# INSGPS.net
KiCad netlist of a schematic drawn in Altium Designer
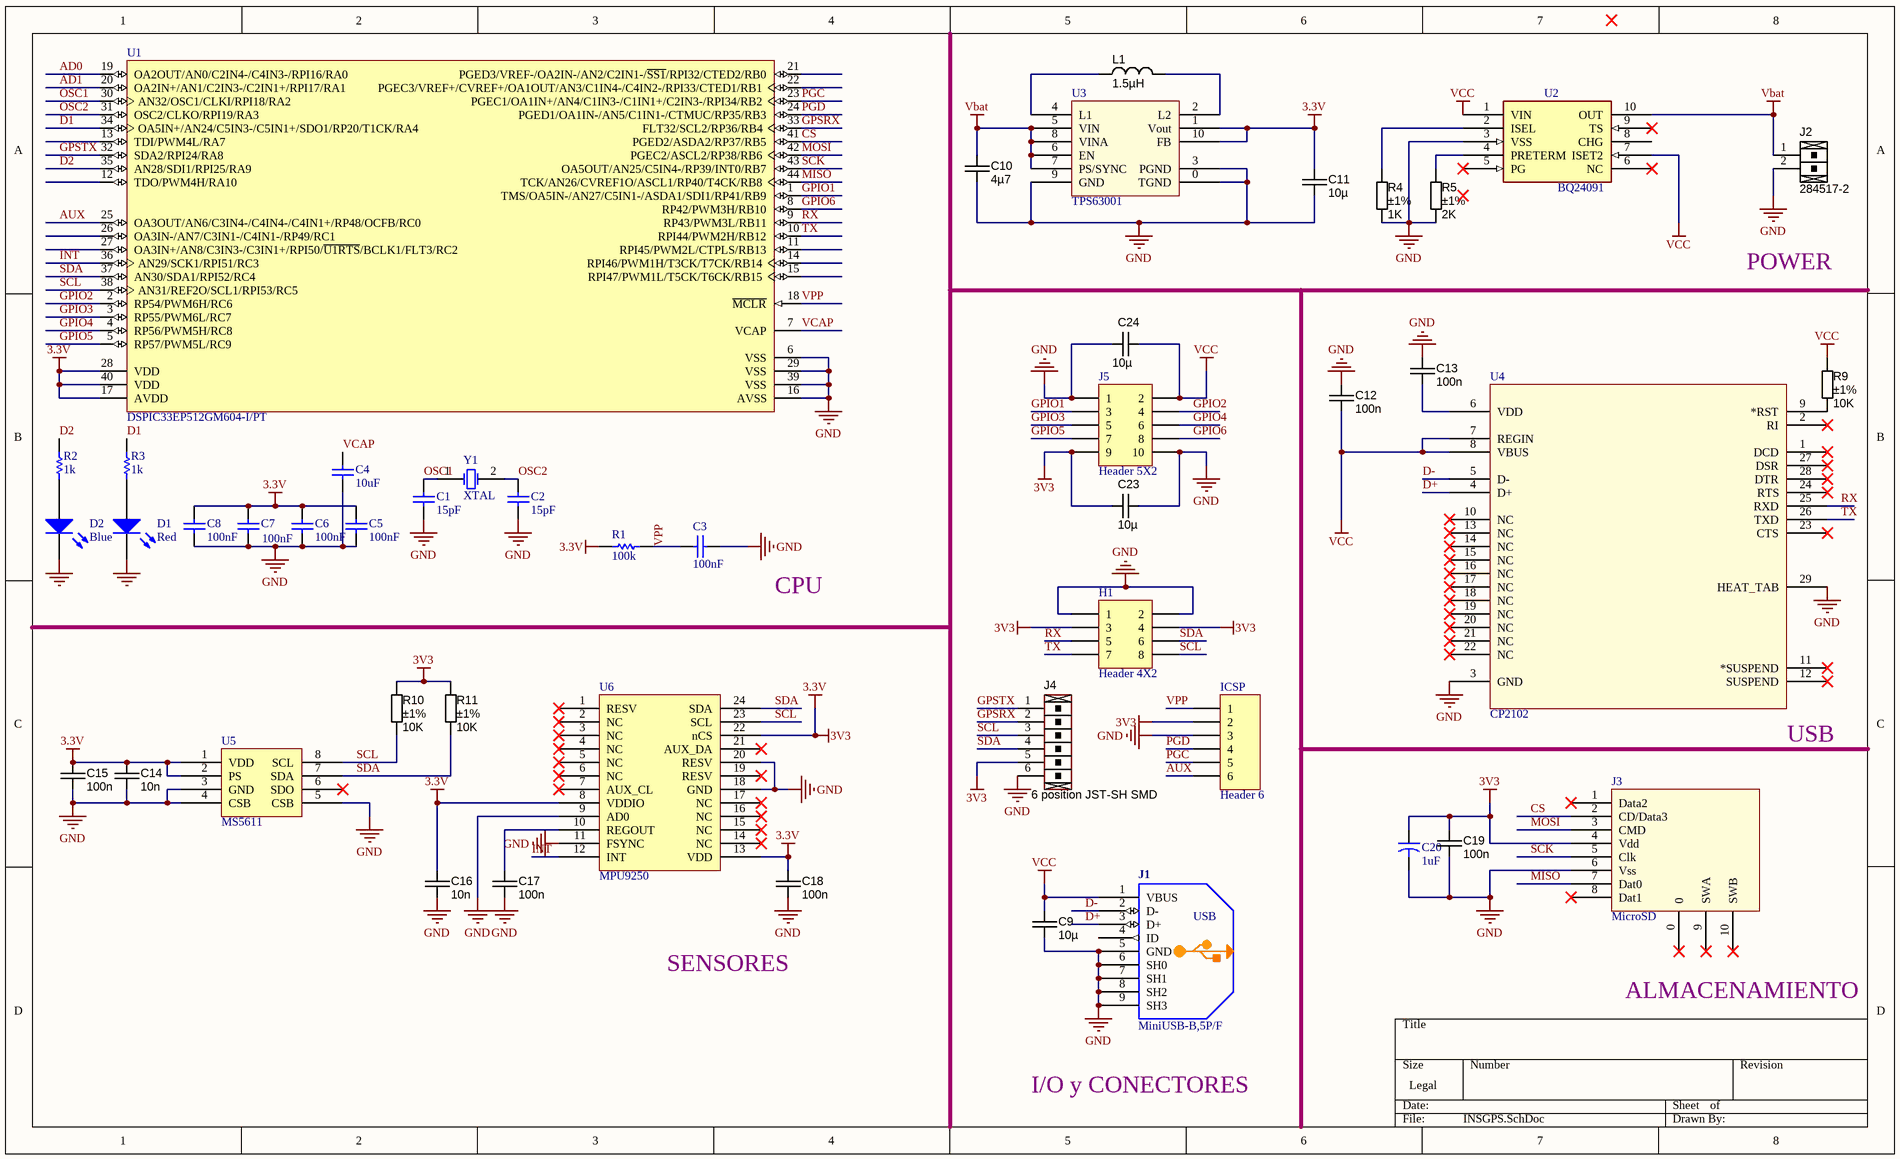
[diagram p0: INSGPS.SchDoc]

(export (version "E")
  (design (tool "Eeschema 10.0.6"))
  (components
    (comp (ref "C1")
      (value "15pF")
      (footprint "C0805")
      (description "Capacitor")
      (fields (field (name "PUBLISHER") "Altium Limited"))
      (libsource (lib "Miscellaneous Devices") (part "Cap"))
    )
    (comp (ref "C2")
      (value "15pF")
      (footprint "C0805")
      (description "Capacitor")
      (fields (field (name "PUBLISHER") "Altium Limited"))
      (libsource (lib "Miscellaneous Devices") (part "Cap"))
    )
    (comp (ref "C3")
      (value "100nF")
      (footprint "C0805")
      (description "Capacitor")
      (fields (field (name "PUBLISHER") "Altium Limited"))
      (libsource (lib "Miscellaneous Devices") (part "Cap"))
    )
    (comp (ref "C4")
      (value "10uF")
      (footprint "C0805")
      (description "Capacitor")
      (fields (field (name "PUBLISHER") "Altium Limited"))
      (libsource (lib "Miscellaneous Devices") (part "Cap"))
    )
    (comp (ref "C5")
      (value "100nF")
      (footprint "C0805")
      (description "Capacitor")
      (fields (field (name "PUBLISHER") "Altium Limited"))
      (libsource (lib "Miscellaneous Devices") (part "Cap"))
    )
    (comp (ref "C6")
      (value "100nF")
      (footprint "C0805")
      (description "Capacitor")
      (fields (field (name "PUBLISHER") "Altium Limited"))
      (libsource (lib "Miscellaneous Devices") (part "Cap"))
    )
    (comp (ref "C7")
      (value "100nF")
      (footprint "C0805")
      (description "Capacitor")
      (fields (field (name "PUBLISHER") "Altium Limited"))
      (libsource (lib "Miscellaneous Devices") (part "Cap"))
    )
    (comp (ref "C8")
      (value "100nF")
      (footprint "C0805")
      (description "Capacitor")
      (fields (field (name "PUBLISHER") "Altium Limited"))
      (libsource (lib "Miscellaneous Devices") (part "Cap"))
    )
    (comp (ref "C9")
      (value "10µ")
      (footprint "CAPC3216X180N")
      (description "Capacitor SMD Cer 10uF 10% 10V X5R 1206")
      (fields (field (name "TOLERANCE") "±10%"))
      (libsource (lib "PBL - Capacitors") (part "CAPC_10u_1206_10V"))
    )
    (comp (ref "C10")
      (value "4µ7")
      (footprint "CAPC2012X135N")
      (description "Capacitor SMD Cer 4.7uF 10% 16V X5R 0805")
      (fields (field (name "TOLERANCE") "±10%"))
      (libsource (lib "PBL - Capacitors") (part "CAPC_4u7_0805"))
    )
    (comp (ref "C11")
      (value "10µ")
      (footprint "CAPC3216X180N")
      (description "Capacitor SMD Cer 10uF 10% 10V X5R 1206")
      (fields (field (name "TOLERANCE") "±10%"))
      (libsource (lib "PBL - Capacitors") (part "CAPC_10u_1206_10V"))
    )
    (comp (ref "C12")
      (value "100n")
      (footprint "CAPC2012X135N")
      (description "Capacitor SMD Cer 100nF 10% 100V X7R 0805")
      (fields (field (name "TOLERANCE") "±10%"))
      (libsource (lib "PBL - Capacitors") (part "CAPC_100n_0805_X7R_100V_10%"))
    )
    (comp (ref "C13")
      (value "100n")
      (footprint "CAPC2012X135N")
      (description "Capacitor SMD Cer 100nF 10% 100V X7R 0805")
      (fields (field (name "TOLERANCE") "±10%"))
      (libsource (lib "PBL - Capacitors") (part "CAPC_100n_0805_X7R_100V_10%"))
    )
    (comp (ref "C14")
      (value "10n")
      (footprint "CAPC2012X135N")
      (description "Capacitor SMD Cer 100nF 10% 100V X7R 0805")
      (fields (field (name "TOLERANCE") "±10%"))
      (libsource (lib "PBL - Capacitors") (part "CAPC_100n_0805_X7R_100V_10%"))
    )
    (comp (ref "C15")
      (value "100n")
      (footprint "CAPC2012X135N")
      (description "Capacitor SMD Cer 100nF 10% 100V X7R 0805")
      (fields (field (name "TOLERANCE") "±10%"))
      (libsource (lib "PBL - Capacitors") (part "CAPC_100n_0805_X7R_100V_10%"))
    )
    (comp (ref "C16")
      (value "10n")
      (footprint "CAPC2012X135N")
      (description "Capacitor SMD Cer 100nF 10% 100V X7R 0805")
      (fields (field (name "TOLERANCE") "±10%"))
      (libsource (lib "PBL - Capacitors") (part "CAPC_100n_0805_X7R_100V_10%"))
    )
    (comp (ref "C17")
      (value "100n")
      (footprint "CAPC2012X135N")
      (description "Capacitor SMD Cer 100nF 10% 100V X7R 0805")
      (fields (field (name "TOLERANCE") "±10%"))
      (libsource (lib "PBL - Capacitors") (part "CAPC_100n_0805_X7R_100V_10%"))
    )
    (comp (ref "C18")
      (value "100n")
      (footprint "CAPC2012X135N")
      (description "Capacitor SMD Cer 100nF 10% 100V X7R 0805")
      (fields (field (name "TOLERANCE") "±10%"))
      (libsource (lib "PBL - Capacitors") (part "CAPC_100n_0805_X7R_100V_10%"))
    )
    (comp (ref "C19")
      (value "100n")
      (footprint "CAPC2012X135N")
      (description "Capacitor SMD Cer 100nF 10% 100V X7R 0805")
      (fields (field (name "TOLERANCE") "±10%"))
      (libsource (lib "PBL - Capacitors") (part "CAPC_100n_0805_X7R_100V_10%"))
    )
    (comp (ref "C20")
      (value "1uF")
      (footprint "CC3216-1206")
      (description "Capacitor Tantalium 1206")
      (fields (field (name "PUBLISHER") "Altium Limited"))
      (libsource (lib "Miscellaneous Devices") (part "Cap2"))
    )
    (comp (ref "C23")
      (value "10µ")
      (footprint "CAPC3216X180N")
      (description "Capacitor SMD Cer 10uF 10% 10V X5R 1206")
      (fields (field (name "TOLERANCE") "±10%"))
      (libsource (lib "PBL - Capacitors") (part "CAPC_10u_1206_10V"))
    )
    (comp (ref "C24")
      (value "10µ")
      (footprint "CAPC3216X180N")
      (description "Capacitor SMD Cer 10uF 10% 10V X5R 1206")
      (fields (field (name "TOLERANCE") "±10%"))
      (libsource (lib "PBL - Capacitors") (part "CAPC_10u_1206_10V"))
    )
    (comp (ref "D1")
      (value "Red")
      (footprint "0805 LED RED")
      (description "Typical BLUE SiC LED")
      (fields (field (name "PUBLISHER") "Altium Limited"))
      (libsource (lib "Miscellaneous Devices") (part "LED3"))
    )
    (comp (ref "D2")
      (value "Blue")
      (footprint "0805 LED RED")
      (description "Typical BLUE SiC LED")
      (fields (field (name "PUBLISHER") "Altium Limited"))
      (libsource (lib "Miscellaneous Devices") (part "LED3"))
    )
    (comp (ref "H1")
      (value "Header 4X2")
      (footprint "HDR2X4")
      (description "Header, 4-Pin, Dual row")
      (fields (field (name "PUBLISHER") "Altium Limited"))
      (libsource (lib "Miscellaneous Connectors") (part "Header 4X2"))
    )
    (comp (ref "ICSP")
      (value "Header 6")
      (footprint "HDR1X6")
      (description "Header, 6-Pin")
      (fields (field (name "PUBLISHER") "Altium Limited"))
      (libsource (lib "Miscellaneous Connectors") (part "Header 6"))
    )
    (comp (ref "J1")
      (value "MiniUSB-B,5P/F")
      (footprint "USB_MINIB_SMT")
      (description "MiniUSB-B,5P/F,7.6×9×4,SMD,RoHS")
      (fields (field (name "Comment") "USB_MINIB_SMT"))
      (libsource (lib "EasyARM-i.MX283-EV") (part "USB_MINIB_SMT"))
    )
    (comp (ref "J2")
      (value "ST 2 pins 1mm pitch")
      (footprint "S2B-PH-K-S")
      (description "Terminal Block THT 2-position header 3.81mm pitch")
      (fields (field (name "VOLTAGE") "300V") (field (name "MANUFACTURER PART NUMBER 1") "284517-2"))
      (libsource (lib "PBL - Connectors") (part "2P_TERM_BLOCK_HEADER"))
    )
    (comp (ref "J3") (value "MicroSD") (footprint "SD CARD") (libsource (lib "TexasLib") (part "MicroSD")))
    (comp (ref "J4")
      (value "6 position JST-SH SMD")
      (footprint "SM06B-SRSS-TB")
      (description "JST-SH, 6-Position connector, 1mm pitch")
      (fields (field (name "VOLTAGE") "300V"))
      (libsource (lib "PBL - Connectors") (part "6P_TERM BLOCK HEADER"))
    )
    (comp (ref "J5")
      (value "Header 5X2")
      (footprint "HDR2X5")
      (description "Header, 5-Pin, Dual row")
      (fields (field (name "PUBLISHER") "Altium Limited"))
      (libsource (lib "Miscellaneous Connectors") (part "Header 5X2"))
    )
    (comp (ref "L1")
      (value "1.5µH")
      (footprint "IND_COILCRAFT_LPS3015")
      (description "Inductor SMD Low DCR 10 µH 900mA 20% 1210")
      (fields (field (name "TOLERANCE") "±20%"))
      (libsource (lib "PBL - Inductors") (part "INDC_10u_LowRDC"))
    )
    (comp (ref "R1")
      (value "100k")
      (footprint "6-0805_M")
      (description "Chip Resistor 0805")
      (fields (field (name "PUBLISHER") "Altium Limited"))
      (libsource (lib "Miscellaneous Devices") (part "Res1"))
    )
    (comp (ref "R2")
      (value "1k")
      (footprint "6-0805_M")
      (description "Chip Resistor 0805")
      (fields (field (name "PUBLISHER") "Altium Limited"))
      (libsource (lib "Miscellaneous Devices") (part "Res1"))
    )
    (comp (ref "R3")
      (value "1k")
      (footprint "6-0805_M")
      (description "Chip Resistor 0805")
      (fields (field (name "PUBLISHER") "Altium Limited"))
      (libsource (lib "Miscellaneous Devices") (part "Res1"))
    )
    (comp (ref "R4")
      (value "1K")
      (footprint "RESC2012X70N")
      (description "Resistor SMD chip 1k Ohm 0.125W 1% 0805")
      (fields (field (name "TOLERANCE") "±1%"))
      (libsource (lib "PBL - Resistors") (part "RES_1K_0805_1%"))
    )
    (comp (ref "R5")
      (value "2K")
      (footprint "RESC2012X70N")
      (description "Resistor SMD chip 1k Ohm 0.125W 1% 0805")
      (fields (field (name "TOLERANCE") "±1%"))
      (libsource (lib "PBL - Resistors") (part "RES_1K_0805_1%"))
    )
    (comp (ref "R9")
      (value "10K")
      (footprint "RESC2012X70N")
      (description "Resistor SMD chip 1k Ohm 0.125W 1% 0805")
      (fields (field (name "TOLERANCE") "±1%"))
      (libsource (lib "PBL - Resistors") (part "RES_1K_0805_1%"))
    )
    (comp (ref "R10")
      (value "10K")
      (footprint "RESC2012X70N")
      (description "Resistor SMD chip 1k Ohm 0.125W 1% 0805")
      (fields (field (name "TOLERANCE") "±1%"))
      (libsource (lib "PBL - Resistors") (part "RES_1K_0805_1%"))
    )
    (comp (ref "R11")
      (value "10K")
      (footprint "RESC2012X70N")
      (description "Resistor SMD chip 1k Ohm 0.125W 1% 0805")
      (fields (field (name "TOLERANCE") "±1%"))
      (libsource (lib "PBL - Resistors") (part "RES_1K_0805_1%"))
    )
    (comp (ref "U1")
      (value "DSPIC33EP512GM604-I/PT")
      (footprint "TQFP-44")
      (fields (field (name "MANUFACTURER") "Microchip"))
      (libsource (lib "Microchip dsPIC33E") (part "DSPIC33EP512GM604-I/PT"))
    )
    (comp (ref "U2")
      (value "BQ24091")
      (footprint "10MSOP-PowerPAD")
      (libsource (lib "ESQUEMATICOS") (part "BQ2409X"))
    )
    (comp (ref "U3")
      (value "TPS63001")
      (footprint "TDFN-EP 10")
      (libsource (lib "ESQUEMATICOS") (part "TPS6303X"))
    )
    (comp (ref "U4")
      (value "CP2102")
      (footprint "QFN50P400X400X95-28N")
      (libsource (lib "ESQUEMATICOS") (part "CP2102"))
    )
    (comp (ref "U5")
      (value "MS5611")
      (footprint "MS5611")
      (description "Sensor digital de presion barometrica absoluta con interfaz I2C")
      (libsource (lib "ESQUEMATICOS") (part "MS5611"))
    )
    (comp (ref "U6")
      (value "MPU9250")
      (footprint "QFN50P400X400X95-24N")
      (libsource (lib "ESQUEMATICOS") (part "MPU9250"))
    )
    (comp (ref "Y1")
      (value "XTAL")
      (footprint "CRYSTAL_NX5032GA / NX5032GB")
      (description "Crystal Oscillator")
      (fields (field (name "PUBLISHER") "Altium Limited"))
      (libsource (lib "Miscellaneous Devices") (part "XTAL"))
    )
  )
  (nets
    (net (code "1") (name "/AD0") (class "Default")
      (node (ref "U1") (pin "19") (pinfunction "OA2OUT/AN0/C2IN4-/C4IN3-/RPI16/RA0_19") (pintype "bidirectional"))
    )
    (net (code "2") (name "/AD1") (class "Default")
      (node (ref "U1") (pin "20") (pinfunction "OA2IN+/AN1/C2IN3-/C2IN1+/RPI17/RA1_20") (pintype "bidirectional"))
    )
    (net (code "3") (name "/AUX") (class "Default")
      (node (ref "ICSP") (pin "6") (pinfunction "6_6") (pintype "passive"))
      (node (ref "U1") (pin "25") (pinfunction "OA3OUT/AN6/C3IN4-/C4IN4-/C4IN1+/RP48/OCFB/RC0_25") (pintype "bidirectional"))
    )
    (net (code "4") (name "/CS") (class "Default")
      (node (ref "J3") (pin "2") (pinfunction "CD/Data3_2") (pintype "passive"))
      (node (ref "U1") (pin "41") (pinfunction "PGED2/ASDA2/RP37/RB5_41") (pintype "bidirectional"))
    )
    (net (code "5") (name "/D+") (class "Default")
      (node (ref "J1") (pin "3") (pinfunction "D+_3") (pintype "bidirectional"))
      (node (ref "U4") (pin "4") (pinfunction "D+_4") (pintype "passive"))
    )
    (net (code "6") (name "/D-") (class "Default")
      (node (ref "J1") (pin "2") (pinfunction "D-_2") (pintype "bidirectional"))
      (node (ref "U4") (pin "5") (pinfunction "D-_5") (pintype "passive"))
    )
    (net (code "7") (name "/D1") (class "Default")
      (node (ref "R3") (pin "1") (pinfunction "1_1") (pintype "passive"))
      (node (ref "U1") (pin "34") (pinfunction "OA5IN+/AN24/C5IN3-/C5IN1+/SDO1/RP20/T1CK/RA4_34") (pintype "bidirectional"))
    )
    (net (code "8") (name "/D2") (class "Default")
      (node (ref "R2") (pin "1") (pinfunction "1_1") (pintype "passive"))
      (node (ref "U1") (pin "35") (pinfunction "AN28/SDI1/RPI25/RA9_35") (pintype "bidirectional"))
    )
    (net (code "9") (name "/GPIO1") (class "Default")
      (node (ref "J5") (pin "3") (pinfunction "3_3") (pintype "passive"))
      (node (ref "U1") (pin "1") (pinfunction "TMS/OA5IN-/AN27/C5IN1-/ASDA1/SDI1/RP41/RB9_1") (pintype "bidirectional"))
    )
    (net (code "10") (name "/GPIO2") (class "Default")
      (node (ref "J5") (pin "4") (pinfunction "4_4") (pintype "passive"))
      (node (ref "U1") (pin "2") (pinfunction "RP54/PWM6H/RC6_2") (pintype "bidirectional"))
    )
    (net (code "11") (name "/GPIO3") (class "Default")
      (node (ref "J5") (pin "5") (pinfunction "5_5") (pintype "passive"))
      (node (ref "U1") (pin "3") (pinfunction "RP55/PWM6L/RC7_3") (pintype "bidirectional"))
    )
    (net (code "12") (name "/GPIO4") (class "Default")
      (node (ref "J5") (pin "6") (pinfunction "6_6") (pintype "passive"))
      (node (ref "U1") (pin "4") (pinfunction "RP56/PWM5H/RC8_4") (pintype "bidirectional"))
    )
    (net (code "13") (name "/GPIO5") (class "Default")
      (node (ref "J5") (pin "7") (pinfunction "7_7") (pintype "passive"))
      (node (ref "U1") (pin "5") (pinfunction "RP57/PWM5L/RC9_5") (pintype "bidirectional"))
    )
    (net (code "14") (name "/GPIO6") (class "Default")
      (node (ref "J5") (pin "8") (pinfunction "8_8") (pintype "passive"))
      (node (ref "U1") (pin "8") (pinfunction "RP42/PWM3H/RB10_8") (pintype "bidirectional"))
    )
    (net (code "15") (name "/GPSRX") (class "Default")
      (node (ref "J4") (pin "2") (pinfunction "2_2") (pintype "passive"))
      (node (ref "U1") (pin "33") (pinfunction "FLT32/SCL2/RP36/RB4_33") (pintype "bidirectional"))
    )
    (net (code "16") (name "/GPSTX") (class "Default")
      (node (ref "J4") (pin "1") (pinfunction "1_1") (pintype "passive"))
      (node (ref "U1") (pin "32") (pinfunction "SDA2/RPI24/RA8_32") (pintype "bidirectional"))
    )
    (net (code "17") (name "/INT") (class "Default")
      (node (ref "U1") (pin "36") (pinfunction "AN29/SCK1/RPI51/RC3_36") (pintype "bidirectional"))
      (node (ref "U6") (pin "12") (pinfunction "INT_12") (pintype "passive"))
    )
    (net (code "18") (name "/MISO") (class "Default")
      (node (ref "J3") (pin "7") (pinfunction "Dat0_7") (pintype "passive"))
      (node (ref "U1") (pin "44") (pinfunction "TCK/AN26/CVREF1O/ASCL1/RP40/T4CK/RB8_44") (pintype "bidirectional"))
    )
    (net (code "19") (name "/MOSI") (class "Default")
      (node (ref "J3") (pin "3") (pinfunction "CMD_3") (pintype "passive"))
      (node (ref "U1") (pin "42") (pinfunction "PGEC2/ASCL2/RP38/RB6_42") (pintype "bidirectional"))
    )
    (net (code "20") (name "/OSC1") (class "Default")
      (node (ref "C1") (pin "2") (pinfunction "2_2") (pintype "passive"))
      (node (ref "U1") (pin "30") (pinfunction "AN32/OSC1/CLKI/RPI18/RA2_30") (pintype "bidirectional"))
      (node (ref "Y1") (pin "1") (pinfunction "OSC1_1") (pintype "passive"))
    )
    (net (code "21") (name "/OSC2") (class "Default")
      (node (ref "C2") (pin "2") (pinfunction "2_2") (pintype "passive"))
      (node (ref "U1") (pin "31") (pinfunction "OSC2/CLKO/RPI19/RA3_31") (pintype "bidirectional"))
      (node (ref "Y1") (pin "2") (pinfunction "OSC2_2") (pintype "passive"))
    )
    (net (code "22") (name "/PGC") (class "Default")
      (node (ref "ICSP") (pin "5") (pinfunction "5_5") (pintype "passive"))
      (node (ref "U1") (pin "23") (pinfunction "PGEC1/OA1IN+/AN4/C1IN3-/C1IN1+/C2IN3-/RPI34/RB2_23") (pintype "bidirectional"))
    )
    (net (code "23") (name "/PGD") (class "Default")
      (node (ref "ICSP") (pin "4") (pinfunction "4_4") (pintype "passive"))
      (node (ref "U1") (pin "24") (pinfunction "PGED1/OA1IN-/AN5/C1IN1-/CTMUC/RP35/RB3_24") (pintype "bidirectional"))
    )
    (net (code "24") (name "/RX") (class "Default")
      (node (ref "H1") (pin "5") (pinfunction "5_5") (pintype "passive"))
      (node (ref "U1") (pin "9") (pinfunction "RP43/PWM3L/RB11_9") (pintype "bidirectional"))
      (node (ref "U4") (pin "25") (pinfunction "RXD_25") (pintype "passive"))
    )
    (net (code "25") (name "/SCK") (class "Default")
      (node (ref "J3") (pin "5") (pinfunction "Clk_5") (pintype "passive"))
      (node (ref "U1") (pin "43") (pinfunction "OA5OUT/AN25/C5IN4-/RP39/INT0/RB7_43") (pintype "bidirectional"))
    )
    (net (code "26") (name "/SCL") (class "Default")
      (node (ref "H1") (pin "8") (pinfunction "8_8") (pintype "passive"))
      (node (ref "J4") (pin "3") (pinfunction "3_3") (pintype "passive"))
      (node (ref "R10") (pin "2") (pinfunction "2_2") (pintype "passive"))
      (node (ref "U1") (pin "38") (pinfunction "AN31/REF2O/SCL1/RPI53/RC5_38") (pintype "bidirectional"))
      (node (ref "U5") (pin "8") (pinfunction "SCL_8") (pintype "passive"))
      (node (ref "U6") (pin "23") (pinfunction "SCL_23") (pintype "passive"))
    )
    (net (code "27") (name "/SDA") (class "Default")
      (node (ref "H1") (pin "6") (pinfunction "6_6") (pintype "passive"))
      (node (ref "J4") (pin "4") (pinfunction "4_4") (pintype "passive"))
      (node (ref "R11") (pin "2") (pinfunction "2_2") (pintype "passive"))
      (node (ref "U1") (pin "37") (pinfunction "AN30/SDA1/RPI52/RC4_37") (pintype "bidirectional"))
      (node (ref "U5") (pin "7") (pinfunction "SDA_7") (pintype "passive"))
      (node (ref "U6") (pin "24") (pinfunction "SDA_24") (pintype "passive"))
    )
    (net (code "28") (name "/TX") (class "Default")
      (node (ref "H1") (pin "7") (pinfunction "7_7") (pintype "passive"))
      (node (ref "U1") (pin "10") (pinfunction "RPI44/PWM2H/RB12_10") (pintype "bidirectional"))
      (node (ref "U4") (pin "26") (pinfunction "TXD_26") (pintype "passive"))
    )
    (net (code "29") (name "/VCAP") (class "Default")
      (node (ref "C4") (pin "2") (pinfunction "2_2") (pintype "passive"))
      (node (ref "U1") (pin "7") (pinfunction "VCAP_7") (pintype "passive"))
    )
    (net (code "30") (name "/VPP") (class "Default")
      (node (ref "C3") (pin "2") (pinfunction "2_2") (pintype "passive"))
      (node (ref "ICSP") (pin "1") (pinfunction "1_1") (pintype "passive"))
      (node (ref "R1") (pin "1") (pinfunction "1_1") (pintype "passive"))
      (node (ref "U1") (pin "18") (pinfunction "~{MCLR}_18") (pintype "input"))
    )
    (net (code "31") (name "3.3V") (class "Default")
      (node (ref "C11") (pin "1") (pintype "passive"))
      (node (ref "C14") (pin "1") (pintype "passive"))
      (node (ref "C15") (pin "1") (pintype "passive"))
      (node (ref "C16") (pin "1") (pintype "passive"))
      (node (ref "C18") (pin "1") (pintype "passive"))
      (node (ref "C19") (pin "1") (pintype "passive"))
      (node (ref "C20") (pin "1") (pinfunction "1_1") (pintype "passive"))
      (node (ref "C23") (pin "1") (pintype "passive"))
      (node (ref "C5") (pin "2") (pinfunction "2_2") (pintype "passive"))
      (node (ref "C6") (pin "1") (pinfunction "1_1") (pintype "passive"))
      (node (ref "C7") (pin "2") (pinfunction "2_2") (pintype "passive"))
      (node (ref "C8") (pin "2") (pinfunction "2_2") (pintype "passive"))
      (node (ref "H1") (pin "3") (pinfunction "3_3") (pintype "passive"))
      (node (ref "H1") (pin "4") (pinfunction "4_4") (pintype "passive"))
      (node (ref "ICSP") (pin "2") (pinfunction "2_2") (pintype "passive"))
      (node (ref "J3") (pin "4") (pinfunction "Vdd_4") (pintype "passive"))
      (node (ref "J4") (pin "5") (pinfunction "5_5") (pintype "passive"))
      (node (ref "J5") (pin "9") (pinfunction "9_9") (pintype "passive"))
      (node (ref "R1") (pin "2") (pinfunction "2_2") (pintype "passive"))
      (node (ref "R10") (pin "1") (pinfunction "1_1") (pintype "passive"))
      (node (ref "R11") (pin "1") (pinfunction "1_1") (pintype "passive"))
      (node (ref "U1") (pin "17") (pinfunction "AVDD_17") (pintype "power_in"))
      (node (ref "U1") (pin "28") (pinfunction "VDD_28") (pintype "power_in"))
      (node (ref "U1") (pin "40") (pinfunction "VDD_40") (pintype "power_in"))
      (node (ref "U3") (pin "1") (pinfunction "Vout_1") (pintype "passive"))
      (node (ref "U3") (pin "10") (pinfunction "FB_10") (pintype "passive"))
      (node (ref "U5") (pin "1") (pinfunction "VDD_1") (pintype "passive"))
      (node (ref "U5") (pin "2") (pinfunction "PS_2") (pintype "passive"))
      (node (ref "U6") (pin "13") (pinfunction "VDD_13") (pintype "passive"))
      (node (ref "U6") (pin "22") (pinfunction "nCS_22") (pintype "passive"))
      (node (ref "U6") (pin "8") (pinfunction "VDDIO_8") (pintype "passive"))
    )
    (net (code "32") (name "GND") (class "Default")
      (node (ref "C1") (pin "1") (pinfunction "1_1") (pintype "passive"))
      (node (ref "C10") (pin "2") (pintype "passive"))
      (node (ref "C11") (pin "2") (pintype "passive"))
      (node (ref "C12") (pin "2") (pintype "passive"))
      (node (ref "C13") (pin "1") (pintype "passive"))
      (node (ref "C14") (pin "2") (pintype "passive"))
      (node (ref "C15") (pin "2") (pintype "passive"))
      (node (ref "C16") (pin "2") (pintype "passive"))
      (node (ref "C17") (pin "2") (pintype "passive"))
      (node (ref "C18") (pin "2") (pintype "passive"))
      (node (ref "C19") (pin "2") (pintype "passive"))
      (node (ref "C2") (pin "1") (pinfunction "1_1") (pintype "passive"))
      (node (ref "C20") (pin "2") (pinfunction "2_2") (pintype "passive"))
      (node (ref "C23") (pin "2") (pintype "passive"))
      (node (ref "C24") (pin "1") (pintype "passive"))
      (node (ref "C3") (pin "1") (pinfunction "1_1") (pintype "passive"))
      (node (ref "C4") (pin "1") (pinfunction "1_1") (pintype "passive"))
      (node (ref "C5") (pin "1") (pinfunction "1_1") (pintype "passive"))
      (node (ref "C6") (pin "2") (pinfunction "2_2") (pintype "passive"))
      (node (ref "C7") (pin "1") (pinfunction "1_1") (pintype "passive"))
      (node (ref "C8") (pin "1") (pinfunction "1_1") (pintype "passive"))
      (node (ref "C9") (pin "2") (pintype "passive"))
      (node (ref "D1") (pin "2") (pinfunction "K_2") (pintype "passive"))
      (node (ref "D2") (pin "2") (pinfunction "K_2") (pintype "passive"))
      (node (ref "H1") (pin "1") (pinfunction "1_1") (pintype "passive"))
      (node (ref "H1") (pin "2") (pinfunction "2_2") (pintype "passive"))
      (node (ref "ICSP") (pin "3") (pinfunction "3_3") (pintype "passive"))
      (node (ref "J1") (pin "5") (pinfunction "GND_5") (pintype "power_in"))
      (node (ref "J1") (pin "6") (pinfunction "SH0_6") (pintype "passive"))
      (node (ref "J1") (pin "7") (pinfunction "SH1_7") (pintype "passive"))
      (node (ref "J1") (pin "8") (pinfunction "SH2_8") (pintype "passive"))
      (node (ref "J1") (pin "9") (pinfunction "SH3_9") (pintype "passive"))
      (node (ref "J2") (pin "2") (pinfunction "2_2") (pintype "passive"))
      (node (ref "J3") (pin "6") (pinfunction "Vss_6") (pintype "passive"))
      (node (ref "J4") (pin "6") (pinfunction "6_6") (pintype "passive"))
      (node (ref "J5") (pin "1") (pinfunction "1_1") (pintype "passive"))
      (node (ref "J5") (pin "10") (pinfunction "10_10") (pintype "passive"))
      (node (ref "R4") (pin "2") (pinfunction "2_2") (pintype "passive"))
      (node (ref "R5") (pin "2") (pinfunction "2_2") (pintype "passive"))
      (node (ref "U1") (pin "16") (pinfunction "AVSS_16") (pintype "power_in"))
      (node (ref "U1") (pin "29") (pinfunction "VSS_29") (pintype "power_in"))
      (node (ref "U1") (pin "39") (pinfunction "VSS_39") (pintype "power_in"))
      (node (ref "U1") (pin "6") (pinfunction "VSS_6") (pintype "power_in"))
      (node (ref "U2") (pin "3") (pinfunction "VSS_3") (pintype "input"))
      (node (ref "U3") (pin "0") (pinfunction "TGND_0") (pintype "passive"))
      (node (ref "U3") (pin "3") (pinfunction "PGND_3") (pintype "passive"))
      (node (ref "U3") (pin "9") (pinfunction "GND_9") (pintype "passive"))
      (node (ref "U4") (pin "29") (pinfunction "HEAT_TAB_29") (pintype "passive"))
      (node (ref "U4") (pin "3") (pinfunction "GND_3") (pintype "passive"))
      (node (ref "U5") (pin "3") (pinfunction "GND_3") (pintype "passive"))
      (node (ref "U5") (pin "4") (pinfunction "CSB_4") (pintype "passive"))
      (node (ref "U5") (pin "5") (pinfunction "CSB_5") (pintype "passive"))
      (node (ref "U6") (pin "11") (pinfunction "FSYNC_11") (pintype "passive"))
      (node (ref "U6") (pin "18") (pinfunction "GND_18") (pintype "passive"))
      (node (ref "U6") (pin "20") (pinfunction "RESV_20") (pintype "passive"))
      (node (ref "U6") (pin "9") (pinfunction "AD0_9") (pintype "passive"))
    )
    (net (code "33") (name "Net-(D1-A)") (class "Default")
      (node (ref "D1") (pin "1") (pinfunction "A_1") (pintype "passive"))
      (node (ref "R3") (pin "2") (pinfunction "2_2") (pintype "passive"))
    )
    (net (code "34") (name "Net-(D2-A)") (class "Default")
      (node (ref "D2") (pin "1") (pinfunction "A_1") (pintype "passive"))
      (node (ref "R2") (pin "2") (pinfunction "2_2") (pintype "passive"))
    )
    (net (code "35") (name "Net-(U2-ISEL)") (class "Default")
      (node (ref "R4") (pin "1") (pinfunction "1_1") (pintype "passive"))
      (node (ref "U2") (pin "2") (pinfunction "ISEL_2") (pintype "passive"))
    )
    (net (code "36") (name "Net-(U2-PRETERM)") (class "Default")
      (node (ref "R5") (pin "1") (pinfunction "1_1") (pintype "passive"))
      (node (ref "U2") (pin "4") (pinfunction "PRETERM_4") (pintype "passive"))
    )
    (net (code "37") (name "Net-(U3-L1)") (class "Default")
      (node (ref "L1") (pin "1") (pinfunction "1_1") (pintype "passive"))
      (node (ref "U3") (pin "4") (pinfunction "L1_4") (pintype "passive"))
    )
    (net (code "38") (name "Net-(U3-L2)") (class "Default")
      (node (ref "L1") (pin "2") (pinfunction "2_2") (pintype "passive"))
      (node (ref "U3") (pin "2") (pinfunction "L2_2") (pintype "passive"))
    )
    (net (code "39") (name "Net-(U4-*RST)") (class "Default")
      (node (ref "R9") (pin "2") (pinfunction "2_2") (pintype "passive"))
      (node (ref "U4") (pin "9") (pinfunction "*RST_9") (pintype "passive"))
    )
    (net (code "40") (name "Net-(U4-VDD)") (class "Default")
      (node (ref "C13") (pin "2") (pintype "passive"))
      (node (ref "U4") (pin "6") (pinfunction "VDD_6") (pintype "passive"))
    )
    (net (code "41") (name "Net-(U6-REGOUT)") (class "Default")
      (node (ref "C17") (pin "1") (pintype "passive"))
      (node (ref "U6") (pin "10") (pinfunction "REGOUT_10") (pintype "passive"))
    )
    (net (code "42") (name "VCC") (class "Default")
      (node (ref "C12") (pin "1") (pintype "passive"))
      (node (ref "C24") (pin "2") (pintype "passive"))
      (node (ref "C9") (pin "1") (pintype "passive"))
      (node (ref "J1") (pin "1") (pinfunction "VBUS_1") (pintype "passive"))
      (node (ref "J5") (pin "2") (pinfunction "2_2") (pintype "passive"))
      (node (ref "R9") (pin "1") (pinfunction "1_1") (pintype "passive"))
      (node (ref "U2") (pin "1") (pinfunction "VIN_1") (pintype "power_in"))
      (node (ref "U2") (pin "7") (pinfunction "ISET2_7") (pintype "input"))
      (node (ref "U4") (pin "7") (pinfunction "REGIN_7") (pintype "passive"))
      (node (ref "U4") (pin "8") (pinfunction "VBUS_8") (pintype "passive"))
    )
    (net (code "43") (name "Vbat") (class "Default")
      (node (ref "C10") (pin "1") (pintype "passive"))
      (node (ref "J2") (pin "1") (pinfunction "1_1") (pintype "passive"))
      (node (ref "U2") (pin "10") (pinfunction "OUT_10") (pintype "power_in"))
      (node (ref "U3") (pin "5") (pinfunction "VIN_5") (pintype "passive"))
      (node (ref "U3") (pin "6") (pinfunction "EN_6") (pintype "passive"))
      (node (ref "U3") (pin "7") (pinfunction "PS/SYNC_7") (pintype "passive"))
      (node (ref "U3") (pin "8") (pinfunction "VINA_8") (pintype "passive"))
    )
    (net (code "44") (name "unconnected-(J1-ID-Pad4)") (class "Default")
      (node (ref "J1") (pin "4") (pinfunction "ID_4") (pintype "output"))
    )
    (net (code "45") (name "unconnected-(J3-Dat1-Pad8)") (class "Default")
      (node (ref "J3") (pin "8") (pinfunction "Dat1_8") (pintype "passive+no_connect"))
    )
    (net (code "46") (name "unconnected-(J3-Data2-Pad1)") (class "Default")
      (node (ref "J3") (pin "1") (pinfunction "Data2_1") (pintype "passive+no_connect"))
    )
    (net (code "47") (name "unconnected-(J3-Pad0)") (class "Default")
      (node (ref "J3") (pin "0") (pinfunction "0_0") (pintype "passive+no_connect"))
    )
    (net (code "48") (name "unconnected-(J3-SWA-Pad9)") (class "Default")
      (node (ref "J3") (pin "9") (pinfunction "SWA_9") (pintype "passive+no_connect"))
    )
    (net (code "49") (name "unconnected-(J3-SWB-Pad10)") (class "Default")
      (node (ref "J3") (pin "10") (pinfunction "SWB_10") (pintype "passive+no_connect"))
    )
    (net (code "50") (name "unconnected-(U1-OA3IN+{slash}AN8{slash}C3IN3-{slash}C3IN1+{slash}RPI50{slash}~{U1RTS}{slash}BCLK1{slash}FLT3{slash}RC2-Pad27)") (class "Default")
      (node (ref "U1") (pin "27") (pinfunction "OA3IN+/AN8/C3IN3-/C3IN1+/RPI50/~{U1RTS}/BCLK1/FLT3/RC2_27") (pintype "bidirectional"))
    )
    (net (code "51") (name "unconnected-(U1-OA3IN-{slash}AN7{slash}C3IN1-{slash}C4IN1-{slash}RP49{slash}RC1-Pad26)") (class "Default")
      (node (ref "U1") (pin "26") (pinfunction "OA3IN-/AN7/C3IN1-/C4IN1-/RP49/RC1_26") (pintype "bidirectional"))
    )
    (net (code "52") (name "unconnected-(U1-PGEC3{slash}VREF+{slash}CVREF+{slash}OA1OUT{slash}AN3{slash}C1IN4-{slash}C4IN2-{slash}RPI33{slash}CTED1{slash}RB1-Pad22)") (class "Default")
      (node (ref "U1") (pin "22") (pinfunction "PGEC3/VREF+/CVREF+/OA1OUT/AN3/C1IN4-/C4IN2-/RPI33/CTED1/RB1_22") (pintype "bidirectional"))
    )
    (net (code "53") (name "unconnected-(U1-PGED3{slash}VREF-{slash}OA2IN-{slash}AN2{slash}C2IN1-{slash}~{SS1}{slash}RPI32{slash}CTED2{slash}RB0-Pad21)") (class "Default")
      (node (ref "U1") (pin "21") (pinfunction "PGED3/VREF-/OA2IN-/AN2/C2IN1-/~{SS1}/RPI32/CTED2/RB0_21") (pintype "bidirectional"))
    )
    (net (code "54") (name "unconnected-(U1-RPI45{slash}PWM2L{slash}CTPLS{slash}RB13-Pad11)") (class "Default")
      (node (ref "U1") (pin "11") (pinfunction "RPI45/PWM2L/CTPLS/RB13_11") (pintype "bidirectional"))
    )
    (net (code "55") (name "unconnected-(U1-RPI46{slash}PWM1H{slash}T3CK{slash}T7CK{slash}RB14-Pad14)") (class "Default")
      (node (ref "U1") (pin "14") (pinfunction "RPI46/PWM1H/T3CK/T7CK/RB14_14") (pintype "bidirectional"))
    )
    (net (code "56") (name "unconnected-(U1-RPI47{slash}PWM1L{slash}T5CK{slash}T6CK{slash}RB15-Pad15)") (class "Default")
      (node (ref "U1") (pin "15") (pinfunction "RPI47/PWM1L/T5CK/T6CK/RB15_15") (pintype "bidirectional"))
    )
    (net (code "57") (name "unconnected-(U1-TDI{slash}PWM4L{slash}RA7-Pad13)") (class "Default")
      (node (ref "U1") (pin "13") (pinfunction "TDI/PWM4L/RA7_13") (pintype "bidirectional"))
    )
    (net (code "58") (name "unconnected-(U1-TDO{slash}PWM4H{slash}RA10-Pad12)") (class "Default")
      (node (ref "U1") (pin "12") (pinfunction "TDO/PWM4H/RA10_12") (pintype "bidirectional"))
    )
    (net (code "59") (name "unconnected-(U2-CHG-Pad8)") (class "Default")
      (node (ref "U2") (pin "8") (pinfunction "CHG_8") (pintype "passive"))
    )
    (net (code "60") (name "unconnected-(U2-NC-Pad6)") (class "Default")
      (node (ref "U2") (pin "6") (pinfunction "NC_6") (pintype "passive+no_connect"))
    )
    (net (code "61") (name "unconnected-(U2-PG-Pad5)") (class "Default")
      (node (ref "U2") (pin "5") (pinfunction "PG_5") (pintype "input+no_connect"))
    )
    (net (code "62") (name "unconnected-(U2-TS-Pad9)") (class "Default")
      (node (ref "U2") (pin "9") (pinfunction "TS_9") (pintype "input+no_connect"))
    )
    (net (code "63") (name "unconnected-(U4-*SUSPEND-Pad11)") (class "Default")
      (node (ref "U4") (pin "11") (pinfunction "*SUSPEND_11") (pintype "passive+no_connect"))
    )
    (net (code "64") (name "unconnected-(U4-CTS-Pad23)") (class "Default")
      (node (ref "U4") (pin "23") (pinfunction "CTS_23") (pintype "passive+no_connect"))
    )
    (net (code "65") (name "unconnected-(U4-DCD-Pad1)") (class "Default")
      (node (ref "U4") (pin "1") (pinfunction "DCD_1") (pintype "passive+no_connect"))
    )
    (net (code "66") (name "unconnected-(U4-DSR-Pad27)") (class "Default")
      (node (ref "U4") (pin "27") (pinfunction "DSR_27") (pintype "passive+no_connect"))
    )
    (net (code "67") (name "unconnected-(U4-DTR-Pad28)") (class "Default")
      (node (ref "U4") (pin "28") (pinfunction "DTR_28") (pintype "passive+no_connect"))
    )
    (net (code "68") (name "unconnected-(U4-NC-Pad10)") (class "Default")
      (node (ref "U4") (pin "10") (pinfunction "NC_10") (pintype "passive+no_connect"))
    )
    (net (code "69") (name "unconnected-(U4-NC-Pad13)") (class "Default")
      (node (ref "U4") (pin "13") (pinfunction "NC_13") (pintype "passive+no_connect"))
    )
    (net (code "70") (name "unconnected-(U4-NC-Pad14)") (class "Default")
      (node (ref "U4") (pin "14") (pinfunction "NC_14") (pintype "passive+no_connect"))
    )
    (net (code "71") (name "unconnected-(U4-NC-Pad15)") (class "Default")
      (node (ref "U4") (pin "15") (pinfunction "NC_15") (pintype "passive+no_connect"))
    )
    (net (code "72") (name "unconnected-(U4-NC-Pad16)") (class "Default")
      (node (ref "U4") (pin "16") (pinfunction "NC_16") (pintype "passive+no_connect"))
    )
    (net (code "73") (name "unconnected-(U4-NC-Pad17)") (class "Default")
      (node (ref "U4") (pin "17") (pinfunction "NC_17") (pintype "passive+no_connect"))
    )
    (net (code "74") (name "unconnected-(U4-NC-Pad18)") (class "Default")
      (node (ref "U4") (pin "18") (pinfunction "NC_18") (pintype "passive+no_connect"))
    )
    (net (code "75") (name "unconnected-(U4-NC-Pad19)") (class "Default")
      (node (ref "U4") (pin "19") (pinfunction "NC_19") (pintype "passive+no_connect"))
    )
    (net (code "76") (name "unconnected-(U4-NC-Pad20)") (class "Default")
      (node (ref "U4") (pin "20") (pinfunction "NC_20") (pintype "passive+no_connect"))
    )
    (net (code "77") (name "unconnected-(U4-NC-Pad21)") (class "Default")
      (node (ref "U4") (pin "21") (pinfunction "NC_21") (pintype "passive+no_connect"))
    )
    (net (code "78") (name "unconnected-(U4-NC-Pad22)") (class "Default")
      (node (ref "U4") (pin "22") (pinfunction "NC_22") (pintype "passive+no_connect"))
    )
    (net (code "79") (name "unconnected-(U4-RI-Pad2)") (class "Default")
      (node (ref "U4") (pin "2") (pinfunction "RI_2") (pintype "passive+no_connect"))
    )
    (net (code "80") (name "unconnected-(U4-RTS-Pad24)") (class "Default")
      (node (ref "U4") (pin "24") (pinfunction "RTS_24") (pintype "passive+no_connect"))
    )
    (net (code "81") (name "unconnected-(U4-SUSPEND-Pad12)") (class "Default")
      (node (ref "U4") (pin "12") (pinfunction "SUSPEND_12") (pintype "passive+no_connect"))
    )
    (net (code "82") (name "unconnected-(U5-SDO-Pad6)") (class "Default")
      (node (ref "U5") (pin "6") (pinfunction "SDO_6") (pintype "passive+no_connect"))
    )
    (net (code "83") (name "unconnected-(U6-AUX_CL-Pad7)") (class "Default")
      (node (ref "U6") (pin "7") (pinfunction "AUX_CL_7") (pintype "passive+no_connect"))
    )
    (net (code "84") (name "unconnected-(U6-AUX_DA-Pad21)") (class "Default")
      (node (ref "U6") (pin "21") (pinfunction "AUX_DA_21") (pintype "passive+no_connect"))
    )
    (net (code "85") (name "unconnected-(U6-NC-Pad2)") (class "Default")
      (node (ref "U6") (pin "2") (pinfunction "NC_2") (pintype "passive+no_connect"))
    )
    (net (code "86") (name "unconnected-(U6-NC-Pad3)") (class "Default")
      (node (ref "U6") (pin "3") (pinfunction "NC_3") (pintype "passive+no_connect"))
    )
    (net (code "87") (name "unconnected-(U6-NC-Pad4)") (class "Default")
      (node (ref "U6") (pin "4") (pinfunction "NC_4") (pintype "passive+no_connect"))
    )
    (net (code "88") (name "unconnected-(U6-NC-Pad5)") (class "Default")
      (node (ref "U6") (pin "5") (pinfunction "NC_5") (pintype "passive+no_connect"))
    )
    (net (code "89") (name "unconnected-(U6-NC-Pad6)") (class "Default")
      (node (ref "U6") (pin "6") (pinfunction "NC_6") (pintype "passive+no_connect"))
    )
    (net (code "90") (name "unconnected-(U6-NC-Pad14)") (class "Default")
      (node (ref "U6") (pin "14") (pinfunction "NC_14") (pintype "passive+no_connect"))
    )
    (net (code "91") (name "unconnected-(U6-NC-Pad15)") (class "Default")
      (node (ref "U6") (pin "15") (pinfunction "NC_15") (pintype "passive+no_connect"))
    )
    (net (code "92") (name "unconnected-(U6-NC-Pad16)") (class "Default")
      (node (ref "U6") (pin "16") (pinfunction "NC_16") (pintype "passive+no_connect"))
    )
    (net (code "93") (name "unconnected-(U6-NC-Pad17)") (class "Default")
      (node (ref "U6") (pin "17") (pinfunction "NC_17") (pintype "passive+no_connect"))
    )
    (net (code "94") (name "unconnected-(U6-RESV-Pad1)") (class "Default")
      (node (ref "U6") (pin "1") (pinfunction "RESV_1") (pintype "passive+no_connect"))
    )
    (net (code "95") (name "unconnected-(U6-RESV-Pad19)") (class "Default")
      (node (ref "U6") (pin "19") (pinfunction "RESV_19") (pintype "passive+no_connect"))
    )
  )
)
